# trackuino_micro_sensor_mk2.net
KiCad netlist of a schematic drawn in EAGLE
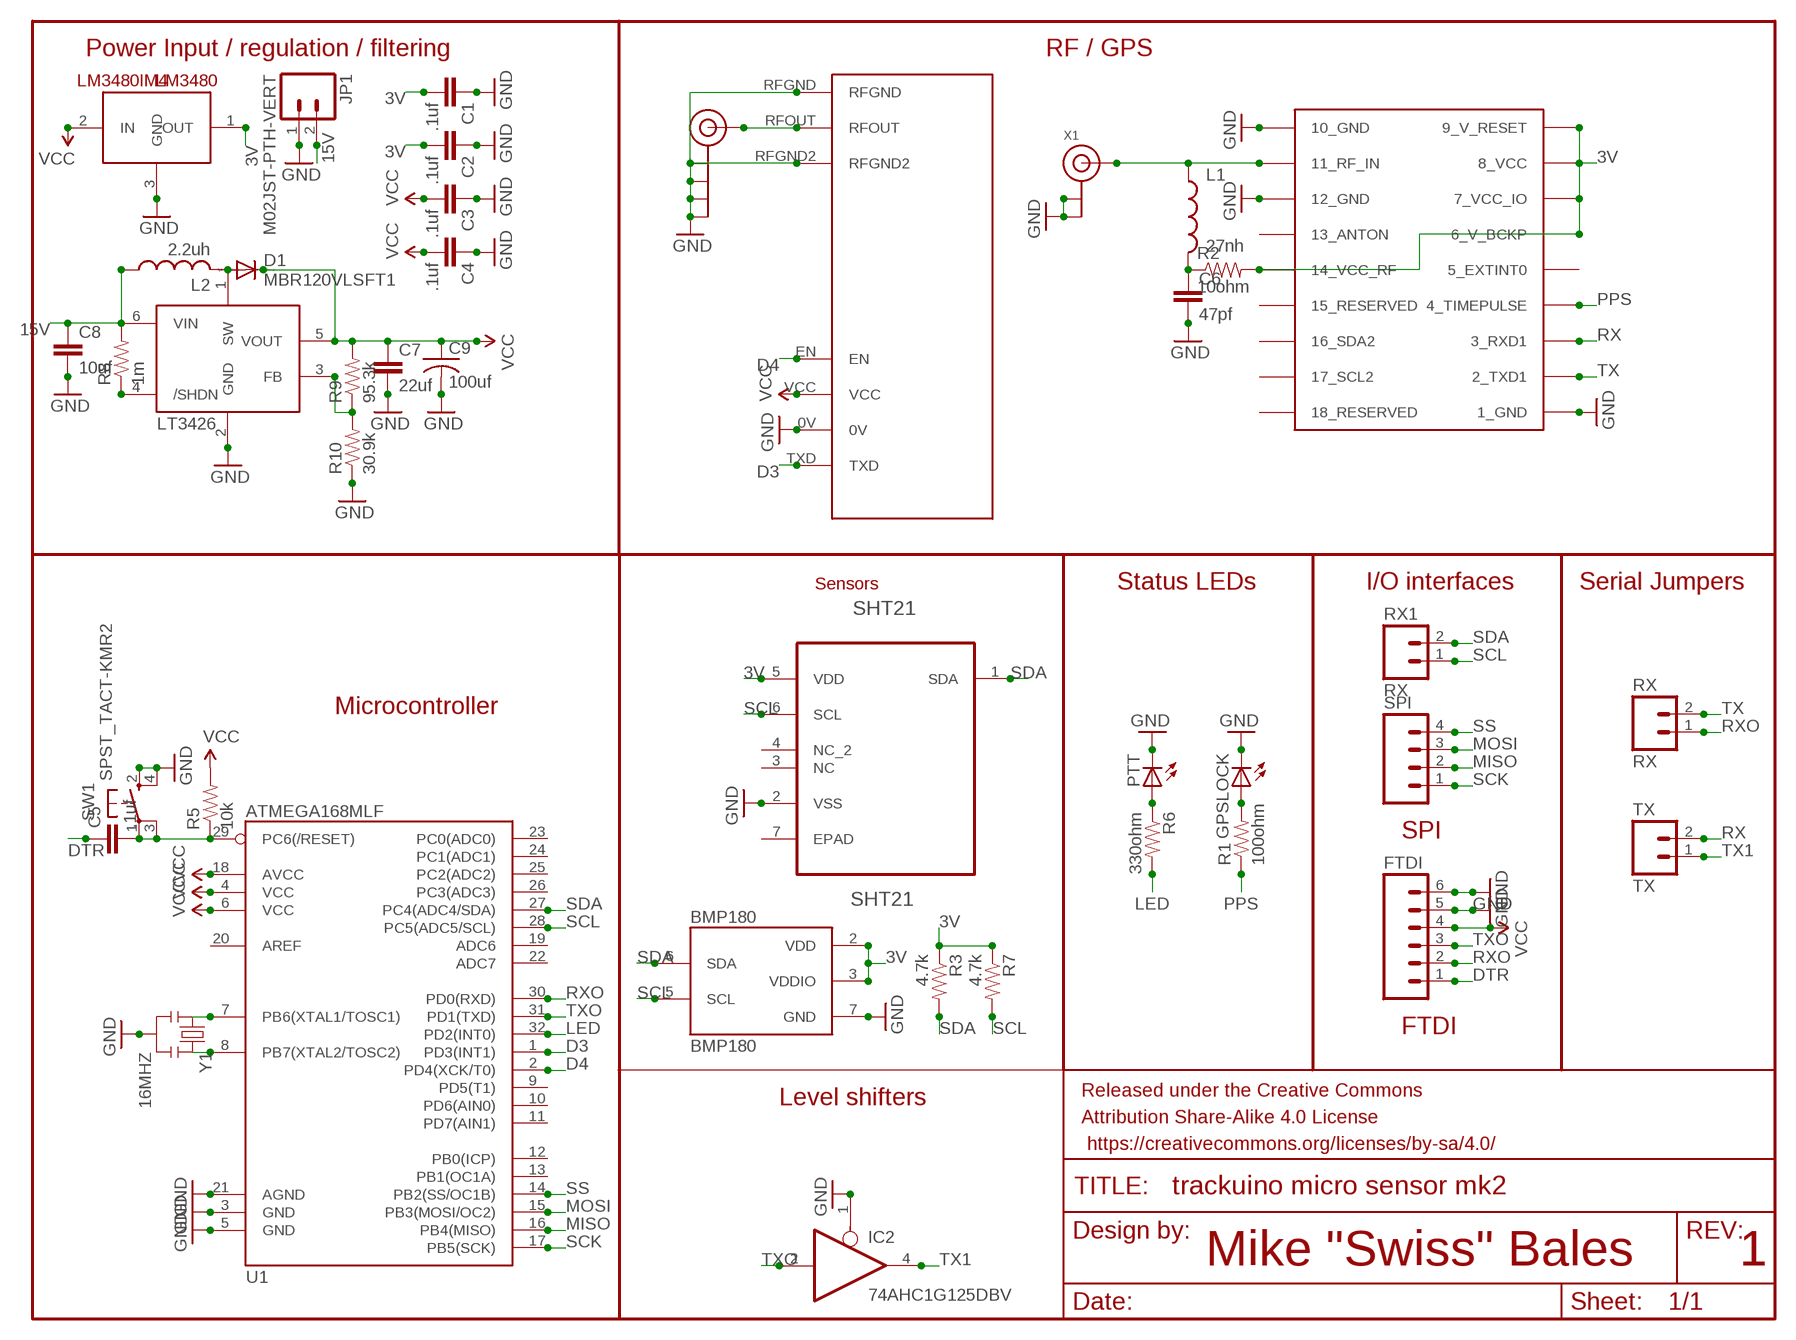
[diagram p0: schematic, sheet 1]

(export (version "E")
  (design (tool "Eeschema 10.0.6"))
  (components
    (comp (ref "BMP180")
      (value "BMP180")
      (footprint "eagle-import:BMP180")
      (libsource (lib "eagle-import") (part "BMP180"))
    )
    (comp (ref "C1")
      (value ".1uf")
      (footprint "eagle-import:0805")
      (libsource (lib "eagle-import") (part "CAP0805"))
    )
    (comp (ref "C2")
      (value ".1uf")
      (footprint "eagle-import:0805")
      (libsource (lib "eagle-import") (part "CAP0805"))
    )
    (comp (ref "C3")
      (value ".1uf")
      (footprint "eagle-import:0805")
      (libsource (lib "eagle-import") (part "CAP0805"))
    )
    (comp (ref "C4")
      (value ".1uf")
      (footprint "eagle-import:0805")
      (libsource (lib "eagle-import") (part "CAP0805"))
    )
    (comp (ref "C5")
      (value ".1uf")
      (footprint "eagle-import:0805")
      (libsource (lib "eagle-import") (part "CAP0805"))
    )
    (comp (ref "C6")
      (value "47pf")
      (footprint "eagle-import:0805")
      (libsource (lib "eagle-import") (part "CAP0805"))
    )
    (comp (ref "C7")
      (value "22uf")
      (footprint "eagle-import:0805")
      (libsource (lib "eagle-import") (part "CAP0805"))
    )
    (comp (ref "C8")
      (value "10uf")
      (footprint "eagle-import:0805")
      (libsource (lib "eagle-import") (part "CAP0805"))
    )
    (comp (ref "C9")
      (value "100uf")
      (footprint "eagle-import:C1206")
      (libsource (lib "eagle-import") (part "C-USC1206"))
    )
    (comp (ref "D1")
      (value "MBR120VLSFT1")
      (footprint "eagle-import:SOD123")
      (libsource (lib "eagle-import") (part "DIODE-SOD123"))
    )
    (comp (ref "FRAME1")
      (value "FRAME-LETTER")
      (footprint "eagle-import:CREATIVE_COMMONS")
      (libsource (lib "eagle-import") (part "FRAME-LETTER"))
    )
    (comp (ref "FTDI")
      (value "M06NO_SILK_FEMALE_PTH")
      (footprint "eagle-import:1X06_NO_SILK")
      (libsource (lib "eagle-import") (part "M06NO_SILK_FEMALE_PTH"))
    )
    (comp (ref "GPSLOCK")
      (value "LEDCHIP-LED0805")
      (footprint "eagle-import:CHIP-LED0805")
      (libsource (lib "eagle-import") (part "LEDCHIP-LED0805"))
    )
    (comp (ref "IC2")
      (value "74AHC1G125DBV")
      (footprint "eagle-import:SOT23-5")
      (libsource (lib "eagle-import") (part "741G125DBVAHC"))
    )
    (comp (ref "J$1")
      (value "SMA_EDGE")
      (footprint "eagle-import:SMA-EDGE")
      (libsource (lib "eagle-import") (part "SMA_EDGE"))
    )
    (comp (ref "JP1")
      (value "M02JST-PTH-VERT")
      (footprint "eagle-import:JST-2-PTH-VERT")
      (libsource (lib "eagle-import") (part "M02JST-PTH-VERT"))
    )
    (comp (ref "L1")
      (value "27nh")
      (footprint "eagle-import:0805")
      (libsource (lib "eagle-import") (part "INDUCTOR0805"))
    )
    (comp (ref "L2")
      (value "2.2uh")
      (footprint "eagle-import:L1812")
      (libsource (lib "eagle-import") (part "L-USL1812"))
    )
    (comp (ref "LM3480")
      (value "LM3480IM4")
      (footprint "eagle-import:SOT23-3")
      (libsource (lib "eagle-import") (part "LM3480IM4"))
    )
    (comp (ref "LT3426")
      (value "LT3426")
      (footprint "eagle-import:SOT23-6")
      (libsource (lib "eagle-import") (part "LT3426"))
    )
    (comp (ref "PTT")
      (value "LEDCHIP-LED0805")
      (footprint "eagle-import:CHIP-LED0805")
      (libsource (lib "eagle-import") (part "LEDCHIP-LED0805"))
    )
    (comp (ref "R1")
      (value "100ohm")
      (footprint "eagle-import:0805")
      (libsource (lib "eagle-import") (part "RESISTOR0805-RES"))
    )
    (comp (ref "R2")
      (value "10ohm")
      (footprint "eagle-import:0805")
      (libsource (lib "eagle-import") (part "RESISTOR0805-RES"))
    )
    (comp (ref "R3")
      (value "4.7k")
      (footprint "eagle-import:0805")
      (libsource (lib "eagle-import") (part "RESISTOR0805-RES"))
    )
    (comp (ref "R5")
      (value "10k")
      (footprint "eagle-import:0805")
      (libsource (lib "eagle-import") (part "RESISTOR0805-RES"))
    )
    (comp (ref "R6")
      (value "330ohm")
      (footprint "eagle-import:0805")
      (libsource (lib "eagle-import") (part "RESISTOR0805-RES"))
    )
    (comp (ref "R7")
      (value "4.7k")
      (footprint "eagle-import:0805")
      (libsource (lib "eagle-import") (part "RESISTOR0805-RES"))
    )
    (comp (ref "R8")
      (value "1m")
      (footprint "eagle-import:0805")
      (libsource (lib "eagle-import") (part "RESISTOR0805-RES"))
    )
    (comp (ref "R9")
      (value "95.3k")
      (footprint "eagle-import:0805")
      (libsource (lib "eagle-import") (part "RESISTOR0805-RES"))
    )
    (comp (ref "R10")
      (value "30.9k")
      (footprint "eagle-import:0805")
      (libsource (lib "eagle-import") (part "RESISTOR0805-RES"))
    )
    (comp (ref "RX")
      (value "RX")
      (footprint "eagle-import:JST-2-PTH-VERT")
      (libsource (lib "eagle-import") (part "M02JST-PTH-VERT"))
    )
    (comp (ref "RX1")
      (value "RX")
      (footprint "eagle-import:JST-2-PTH-VERT")
      (libsource (lib "eagle-import") (part "M02JST-PTH-VERT"))
    )
    (comp (ref "SHT21")
      (value "SHT21")
      (footprint "eagle-import:DFN300X300X110-7N")
      (libsource (lib "eagle-import") (part "SHT21"))
    )
    (comp (ref "SPI")
      (value "M04JST-PTH-VERT")
      (footprint "eagle-import:JST-4-PTH-VERT")
      (libsource (lib "eagle-import") (part "M04JST-PTH-VERT"))
    )
    (comp (ref "SW1")
      (value "SPST_TACT-KMR2")
      (footprint "eagle-import:KMR2")
      (libsource (lib "eagle-import") (part "SPST_TACT-KMR2"))
    )
    (comp (ref "TX")
      (value "TX")
      (footprint "eagle-import:JST-2-PTH-VERT")
      (libsource (lib "eagle-import") (part "M02JST-PTH-VERT"))
    )
    (comp (ref "U$1")
      (value "UBLOX_MAX")
      (footprint "eagle-import:UBLOX_MAX")
      (libsource (lib "eagle-import") (part "UBLOX_MAX"))
    )
    (comp (ref "U$2")
      (value "RADIOMETRIX-HX1")
      (footprint "eagle-import:RADIOMETRIX-HX1")
      (libsource (lib "eagle-import") (part "RADIOMETRIX-HX1"))
    )
    (comp (ref "U1")
      (value "ATMEGA168MLF")
      (footprint "eagle-import:MLF32")
      (libsource (lib "eagle-import") (part "ATMEGA168MLF"))
    )
    (comp (ref "X1")
      (value "ANTENNA_U.FL")
      (footprint "eagle-import:U.FL")
      (libsource (lib "eagle-import") (part "ANTENNA_U.FL"))
    )
    (comp (ref "Y1")
      (value "16MHZ")
      (footprint "eagle-import:RESONATOR-SMD")
      (libsource (lib "eagle-import") (part "RESONATOR16MHZ"))
    )
  )
  (nets
    (net (code "1") (name "/3V") (class "Default")
      (node (ref "BMP180") (pin "2") (pinfunction "VDD_2") (pintype "power_in"))
      (node (ref "BMP180") (pin "3") (pinfunction "VDDIO_3") (pintype "power_in"))
      (node (ref "C1") (pin "2") (pinfunction "2_2") (pintype "passive"))
      (node (ref "C2") (pin "2") (pinfunction "2_2") (pintype "passive"))
      (node (ref "LM3480") (pin "1") (pinfunction "OUT_1") (pintype "bidirectional"))
      (node (ref "R2") (pin "2") (pinfunction "2_2") (pintype "passive"))
      (node (ref "R3") (pin "1") (pinfunction "1_1") (pintype "passive"))
      (node (ref "R7") (pin "1") (pinfunction "1_1") (pintype "passive"))
      (node (ref "SHT21") (pin "5") (pinfunction "VDD_5") (pintype "power_in"))
      (node (ref "U$1") (pin "14_VCC_RF") (pinfunction "14_VCC_RF_14_VCC_RF") (pintype "bidirectional"))
      (node (ref "U$1") (pin "6_V_BCKP") (pinfunction "6_V_BCKP_6_V_BCKP") (pintype "bidirectional"))
      (node (ref "U$1") (pin "7_VCC_IO") (pinfunction "7_VCC_IO_7_VCC_IO") (pintype "power_in"))
      (node (ref "U$1") (pin "8_VCC") (pinfunction "8_VCC_8_VCC") (pintype "power_in"))
      (node (ref "U$1") (pin "9_V_RESET") (pinfunction "9_V_RESET_9_V_RESET") (pintype "power_in"))
    )
    (net (code "2") (name "/15V") (class "Default")
      (node (ref "C8") (pin "1") (pinfunction "1_1") (pintype "passive"))
      (node (ref "JP1") (pin "2") (pinfunction "2_2") (pintype "passive"))
      (node (ref "L2") (pin "1") (pinfunction "1_1") (pintype "passive"))
      (node (ref "LT3426") (pin "6") (pinfunction "VIN_6") (pintype "input"))
      (node (ref "R8") (pin "2") (pinfunction "2_2") (pintype "passive"))
    )
    (net (code "3") (name "/D3") (class "Default")
      (node (ref "U$2") (pin "TXD") (pinfunction "TXD_TXD") (pintype "bidirectional"))
      (node (ref "U1") (pin "1") (pinfunction "PD3(INT1)_1") (pintype "bidirectional"))
    )
    (net (code "4") (name "/D4") (class "Default")
      (node (ref "U$2") (pin "EN") (pinfunction "EN_EN") (pintype "bidirectional"))
      (node (ref "U1") (pin "2") (pinfunction "PD4(XCK/T0)_2") (pintype "bidirectional"))
    )
    (net (code "5") (name "/DTR") (class "Default")
      (node (ref "C5") (pin "1") (pinfunction "1_1") (pintype "passive"))
      (node (ref "FTDI") (pin "1") (pinfunction "1_1") (pintype "passive"))
    )
    (net (code "6") (name "/LED") (class "Default")
      (node (ref "R6") (pin "2") (pinfunction "2_2") (pintype "passive"))
      (node (ref "U1") (pin "32") (pinfunction "PD2(INT0)_32") (pintype "bidirectional"))
    )
    (net (code "7") (name "/MISO") (class "Default")
      (node (ref "SPI") (pin "2") (pinfunction "2_2") (pintype "passive"))
      (node (ref "U1") (pin "16") (pinfunction "PB4(MISO)_16") (pintype "bidirectional"))
    )
    (net (code "8") (name "/MOSI") (class "Default")
      (node (ref "SPI") (pin "3") (pinfunction "3_3") (pintype "passive"))
      (node (ref "U1") (pin "15") (pinfunction "PB3(MOSI/OC2)_15") (pintype "bidirectional"))
    )
    (net (code "9") (name "/PPS") (class "Default")
      (node (ref "R1") (pin "1") (pinfunction "1_1") (pintype "passive"))
      (node (ref "U$1") (pin "4_TIMEPULSE") (pinfunction "4_TIMEPULSE_4_TIMEPULSE") (pintype "bidirectional"))
    )
    (net (code "10") (name "/RX") (class "Default")
      (node (ref "TX") (pin "2") (pinfunction "2_2") (pintype "passive"))
      (node (ref "U$1") (pin "3_RXD1") (pinfunction "3_RXD1_3_RXD1") (pintype "bidirectional"))
    )
    (net (code "11") (name "/RXO") (class "Default")
      (node (ref "FTDI") (pin "2") (pinfunction "2_2") (pintype "passive"))
      (node (ref "RX") (pin "1") (pinfunction "1_1") (pintype "passive"))
      (node (ref "U1") (pin "30") (pinfunction "PD0(RXD)_30") (pintype "bidirectional"))
    )
    (net (code "12") (name "/SCK") (class "Default")
      (node (ref "SPI") (pin "1") (pinfunction "1_1") (pintype "passive"))
      (node (ref "U1") (pin "17") (pinfunction "PB5(SCK)_17") (pintype "bidirectional"))
    )
    (net (code "13") (name "/SCL") (class "Default")
      (node (ref "BMP180") (pin "5") (pinfunction "SCL_5") (pintype "input"))
      (node (ref "R7") (pin "2") (pinfunction "2_2") (pintype "passive"))
      (node (ref "RX1") (pin "1") (pinfunction "1_1") (pintype "passive"))
      (node (ref "SHT21") (pin "6") (pinfunction "SCL_6") (pintype "input"))
      (node (ref "U1") (pin "28") (pinfunction "PC5(ADC5/SCL)_28") (pintype "bidirectional"))
    )
    (net (code "14") (name "/SDA") (class "Default")
      (node (ref "BMP180") (pin "6") (pinfunction "SDA_6") (pintype "bidirectional"))
      (node (ref "R3") (pin "2") (pinfunction "2_2") (pintype "passive"))
      (node (ref "RX1") (pin "2") (pinfunction "2_2") (pintype "passive"))
      (node (ref "SHT21") (pin "1") (pinfunction "SDA_1") (pintype "bidirectional"))
      (node (ref "U1") (pin "27") (pinfunction "PC4(ADC4/SDA)_27") (pintype "bidirectional"))
    )
    (net (code "15") (name "/SS") (class "Default")
      (node (ref "SPI") (pin "4") (pinfunction "4_4") (pintype "passive"))
      (node (ref "U1") (pin "14") (pinfunction "PB2(SS/OC1B)_14") (pintype "bidirectional"))
    )
    (net (code "16") (name "/TX") (class "Default")
      (node (ref "RX") (pin "2") (pinfunction "2_2") (pintype "passive"))
      (node (ref "U$1") (pin "2_TXD1") (pinfunction "2_TXD1_2_TXD1") (pintype "bidirectional"))
    )
    (net (code "17") (name "/TX1") (class "Default")
      (node (ref "IC2") (pin "4") (pinfunction "O_4") (pintype "tri_state"))
      (node (ref "TX") (pin "1") (pinfunction "1_1") (pintype "passive"))
    )
    (net (code "18") (name "/TXO") (class "Default")
      (node (ref "FTDI") (pin "3") (pinfunction "3_3") (pintype "passive"))
      (node (ref "IC2") (pin "2") (pinfunction "I_2") (pintype "input"))
      (node (ref "U1") (pin "31") (pinfunction "PD1(TXD)_31") (pintype "bidirectional"))
    )
    (net (code "19") (name "GND") (class "Default")
      (node (ref "BMP180") (pin "7") (pinfunction "GND_7") (pintype "power_in"))
      (node (ref "C1") (pin "1") (pinfunction "1_1") (pintype "passive"))
      (node (ref "C2") (pin "1") (pinfunction "1_1") (pintype "passive"))
      (node (ref "C3") (pin "1") (pinfunction "1_1") (pintype "passive"))
      (node (ref "C4") (pin "1") (pinfunction "1_1") (pintype "passive"))
      (node (ref "C6") (pin "2") (pinfunction "2_2") (pintype "passive"))
      (node (ref "C7") (pin "2") (pinfunction "2_2") (pintype "passive"))
      (node (ref "C8") (pin "2") (pinfunction "2_2") (pintype "passive"))
      (node (ref "C9") (pin "2") (pinfunction "2_2") (pintype "passive"))
      (node (ref "FTDI") (pin "5") (pinfunction "5_5") (pintype "passive"))
      (node (ref "FTDI") (pin "6") (pinfunction "6_6") (pintype "passive"))
      (node (ref "GPSLOCK") (pin "C") (pinfunction "C_C") (pintype "passive"))
      (node (ref "IC2") (pin "1") (pinfunction "OE_1") (pintype "input"))
      (node (ref "J$1") (pin "GND@0") (pinfunction "GND_GND@0") (pintype "bidirectional"))
      (node (ref "J$1") (pin "GND@1") (pinfunction "GND_GND@1") (pintype "bidirectional"))
      (node (ref "J$1") (pin "GND@2") (pinfunction "GND_GND@2") (pintype "bidirectional"))
      (node (ref "J$1") (pin "GND@3") (pinfunction "GND_GND@3") (pintype "bidirectional"))
      (node (ref "JP1") (pin "1") (pinfunction "1_1") (pintype "passive"))
      (node (ref "LM3480") (pin "3") (pinfunction "GND_3") (pintype "bidirectional"))
      (node (ref "LT3426") (pin "2") (pinfunction "GND_2") (pintype "power_in"))
      (node (ref "PTT") (pin "C") (pinfunction "C_C") (pintype "passive"))
      (node (ref "R10") (pin "1") (pinfunction "1_1") (pintype "passive"))
      (node (ref "SHT21") (pin "2") (pinfunction "VSS_2") (pintype "power_in"))
      (node (ref "SW1") (pin "2") (pinfunction "S_2") (pintype "passive"))
      (node (ref "SW1") (pin "4") (pinfunction "S1_4") (pintype "passive"))
      (node (ref "U$1") (pin "10_GND") (pinfunction "10_GND_10_GND") (pintype "power_in"))
      (node (ref "U$1") (pin "12_GND") (pinfunction "12_GND_12_GND") (pintype "power_in"))
      (node (ref "U$1") (pin "1_GND") (pinfunction "1_GND_1_GND") (pintype "power_in"))
      (node (ref "U$2") (pin "0V") (pinfunction "0V_0V") (pintype "bidirectional"))
      (node (ref "U$2") (pin "RFGND") (pinfunction "RFGND_RFGND") (pintype "bidirectional"))
      (node (ref "U$2") (pin "RFGND2") (pinfunction "RFGND2_RFGND2") (pintype "bidirectional"))
      (node (ref "U1") (pin "21") (pinfunction "AGND_21") (pintype "bidirectional"))
      (node (ref "U1") (pin "3") (pinfunction "GND_3") (pintype "bidirectional"))
      (node (ref "U1") (pin "5") (pinfunction "GND_5") (pintype "bidirectional"))
      (node (ref "X1") (pin "1") (pinfunction "GND_1") (pintype "passive"))
      (node (ref "X1") (pin "2") (pinfunction "GND_2") (pintype "passive"))
      (node (ref "Y1") (pin "2") (pinfunction "2_2") (pintype "passive"))
    )
    (net (code "20") (name "Net-(C6-Pad1)") (class "Default")
      (node (ref "C6") (pin "1") (pinfunction "1_1") (pintype "passive"))
      (node (ref "L1") (pin "2") (pinfunction "2_2") (pintype "passive"))
      (node (ref "R2") (pin "1") (pinfunction "1_1") (pintype "passive"))
    )
    (net (code "21") (name "Net-(GPSLOCK-PadA)") (class "Default")
      (node (ref "GPSLOCK") (pin "A") (pinfunction "A_A") (pintype "passive"))
      (node (ref "R1") (pin "2") (pinfunction "2_2") (pintype "passive"))
    )
    (net (code "22") (name "Net-(J$1-SIGNAL)") (class "Default")
      (node (ref "J$1") (pin "SIG") (pinfunction "SIGNAL_SIG") (pintype "bidirectional"))
      (node (ref "U$2") (pin "RFOUT") (pinfunction "RFOUT_RFOUT") (pintype "bidirectional"))
    )
    (net (code "23") (name "Net-(LT3426-FB)") (class "Default")
      (node (ref "LT3426") (pin "3") (pinfunction "FB_3") (pintype "input"))
      (node (ref "R10") (pin "2") (pinfunction "2_2") (pintype "passive"))
      (node (ref "R9") (pin "1") (pinfunction "1_1") (pintype "passive"))
    )
    (net (code "24") (name "Net-(LT3426-SW)") (class "Default")
      (node (ref "D1") (pin "A") (pinfunction "A_A") (pintype "passive"))
      (node (ref "L2") (pin "2") (pinfunction "2_2") (pintype "passive"))
      (node (ref "LT3426") (pin "1") (pinfunction "SW_1") (pintype "output"))
    )
    (net (code "25") (name "Net-(LT3426-{slash}SHDN)") (class "Default")
      (node (ref "LT3426") (pin "4") (pinfunction "/SHDN_4") (pintype "input"))
      (node (ref "R8") (pin "1") (pinfunction "1_1") (pintype "passive"))
    )
    (net (code "26") (name "Net-(PTT-PadA)") (class "Default")
      (node (ref "PTT") (pin "A") (pinfunction "A_A") (pintype "passive"))
      (node (ref "R6") (pin "1") (pinfunction "1_1") (pintype "passive"))
    )
    (net (code "27") (name "Net-(SW1-P)") (class "Default")
      (node (ref "C5") (pin "2") (pinfunction "2_2") (pintype "passive"))
      (node (ref "R5") (pin "1") (pinfunction "1_1") (pintype "passive"))
      (node (ref "SW1") (pin "1") (pinfunction "P_1") (pintype "passive"))
      (node (ref "SW1") (pin "3") (pinfunction "P1_3") (pintype "passive"))
      (node (ref "U1") (pin "29") (pinfunction "PC6(/RESET)_29") (pintype "bidirectional"))
    )
    (net (code "28") (name "Net-(U1-PB6(XTAL1{slash}TOSC1))") (class "Default")
      (node (ref "U1") (pin "7") (pinfunction "PB6(XTAL1/TOSC1)_7") (pintype "bidirectional"))
      (node (ref "Y1") (pin "1") (pinfunction "1_1") (pintype "passive"))
    )
    (net (code "29") (name "Net-(U1-PB7(XTAL2{slash}TOSC2))") (class "Default")
      (node (ref "U1") (pin "8") (pinfunction "PB7(XTAL2/TOSC2)_8") (pintype "bidirectional"))
      (node (ref "Y1") (pin "3") (pinfunction "3_3") (pintype "passive"))
    )
    (net (code "30") (name "Net-(X1-SIGNAL)") (class "Default")
      (node (ref "L1") (pin "1") (pinfunction "1_1") (pintype "passive"))
      (node (ref "U$1") (pin "11_RF_IN") (pinfunction "11_RF_IN_11_RF_IN") (pintype "bidirectional"))
      (node (ref "X1") (pin "3") (pinfunction "SIGNAL_3") (pintype "passive"))
    )
    (net (code "31") (name "VCC") (class "Default")
      (node (ref "C3") (pin "2") (pinfunction "2_2") (pintype "passive"))
      (node (ref "C4") (pin "2") (pinfunction "2_2") (pintype "passive"))
      (node (ref "C7") (pin "1") (pinfunction "1_1") (pintype "passive"))
      (node (ref "C9") (pin "1") (pinfunction "1_1") (pintype "passive"))
      (node (ref "D1") (pin "C") (pinfunction "C_C") (pintype "passive"))
      (node (ref "FTDI") (pin "4") (pinfunction "4_4") (pintype "passive"))
      (node (ref "LM3480") (pin "2") (pinfunction "IN_2") (pintype "bidirectional"))
      (node (ref "LT3426") (pin "5") (pinfunction "VOUT_5") (pintype "output"))
      (node (ref "R5") (pin "2") (pinfunction "2_2") (pintype "passive"))
      (node (ref "R9") (pin "2") (pinfunction "2_2") (pintype "passive"))
      (node (ref "U$2") (pin "VCC") (pinfunction "VCC_VCC") (pintype "bidirectional"))
      (node (ref "U1") (pin "18") (pinfunction "AVCC_18") (pintype "bidirectional"))
      (node (ref "U1") (pin "4") (pinfunction "VCC_4") (pintype "bidirectional"))
      (node (ref "U1") (pin "6") (pinfunction "VCC_6") (pintype "bidirectional"))
    )
    (net (code "32") (name "unconnected-(SHT21-EPAD-Pad7)") (class "Default")
      (node (ref "SHT21") (pin "7") (pinfunction "EPAD_7") (pintype "passive"))
    )
    (net (code "33") (name "unconnected-(SHT21-NC-Pad3)") (class "Default")
      (node (ref "SHT21") (pin "3") (pinfunction "NC_3") (pintype "no_connect"))
    )
    (net (code "34") (name "unconnected-(SHT21-NC_2-Pad4)") (class "Default")
      (node (ref "SHT21") (pin "4") (pinfunction "NC_2_4") (pintype "no_connect"))
    )
    (net (code "35") (name "unconnected-(U$1-Pad5_EXTINT0)") (class "Default")
      (node (ref "U$1") (pin "5_EXTINT0") (pinfunction "5_EXTINT0_5_EXTINT0") (pintype "bidirectional"))
    )
    (net (code "36") (name "unconnected-(U$1-Pad13_ANTON)") (class "Default")
      (node (ref "U$1") (pin "13_ANTON") (pinfunction "13_ANTON_13_ANTON") (pintype "bidirectional"))
    )
    (net (code "37") (name "unconnected-(U$1-Pad15_RESERVED)") (class "Default")
      (node (ref "U$1") (pin "15_RESERVED") (pinfunction "15_RESERVED_15_RESERVED") (pintype "bidirectional"))
    )
    (net (code "38") (name "unconnected-(U$1-Pad16_SDA2)") (class "Default")
      (node (ref "U$1") (pin "16_SDA2") (pinfunction "16_SDA2_16_SDA2") (pintype "bidirectional"))
    )
    (net (code "39") (name "unconnected-(U$1-Pad17_SCL2)") (class "Default")
      (node (ref "U$1") (pin "17_SCL2") (pinfunction "17_SCL2_17_SCL2") (pintype "bidirectional"))
    )
    (net (code "40") (name "unconnected-(U$1-Pad18_RESERVED)") (class "Default")
      (node (ref "U$1") (pin "18_RESERVED") (pinfunction "18_RESERVED_18_RESERVED") (pintype "bidirectional"))
    )
    (net (code "41") (name "unconnected-(U1-ADC6-Pad19)") (class "Default")
      (node (ref "U1") (pin "19") (pinfunction "ADC6_19") (pintype "bidirectional"))
    )
    (net (code "42") (name "unconnected-(U1-ADC7-Pad22)") (class "Default")
      (node (ref "U1") (pin "22") (pinfunction "ADC7_22") (pintype "bidirectional"))
    )
    (net (code "43") (name "unconnected-(U1-AREF-Pad20)") (class "Default")
      (node (ref "U1") (pin "20") (pinfunction "AREF_20") (pintype "bidirectional"))
    )
    (net (code "44") (name "unconnected-(U1-PB0(ICP)-Pad12)") (class "Default")
      (node (ref "U1") (pin "12") (pinfunction "PB0(ICP)_12") (pintype "bidirectional"))
    )
    (net (code "45") (name "unconnected-(U1-PB1(OC1A)-Pad13)") (class "Default")
      (node (ref "U1") (pin "13") (pinfunction "PB1(OC1A)_13") (pintype "bidirectional"))
    )
    (net (code "46") (name "unconnected-(U1-PC0(ADC0)-Pad23)") (class "Default")
      (node (ref "U1") (pin "23") (pinfunction "PC0(ADC0)_23") (pintype "bidirectional"))
    )
    (net (code "47") (name "unconnected-(U1-PC1(ADC1)-Pad24)") (class "Default")
      (node (ref "U1") (pin "24") (pinfunction "PC1(ADC1)_24") (pintype "bidirectional"))
    )
    (net (code "48") (name "unconnected-(U1-PC2(ADC2)-Pad25)") (class "Default")
      (node (ref "U1") (pin "25") (pinfunction "PC2(ADC2)_25") (pintype "bidirectional"))
    )
    (net (code "49") (name "unconnected-(U1-PC3(ADC3)-Pad26)") (class "Default")
      (node (ref "U1") (pin "26") (pinfunction "PC3(ADC3)_26") (pintype "bidirectional"))
    )
    (net (code "50") (name "unconnected-(U1-PD5(T1)-Pad9)") (class "Default")
      (node (ref "U1") (pin "9") (pinfunction "PD5(T1)_9") (pintype "bidirectional"))
    )
    (net (code "51") (name "unconnected-(U1-PD6(AIN0)-Pad10)") (class "Default")
      (node (ref "U1") (pin "10") (pinfunction "PD6(AIN0)_10") (pintype "bidirectional"))
    )
    (net (code "52") (name "unconnected-(U1-PD7(AIN1)-Pad11)") (class "Default")
      (node (ref "U1") (pin "11") (pinfunction "PD7(AIN1)_11") (pintype "bidirectional"))
    )
  )
)
